# OpenMPPT2-Supply.net
KiCad netlist of a schematic drawn in Altium Designer
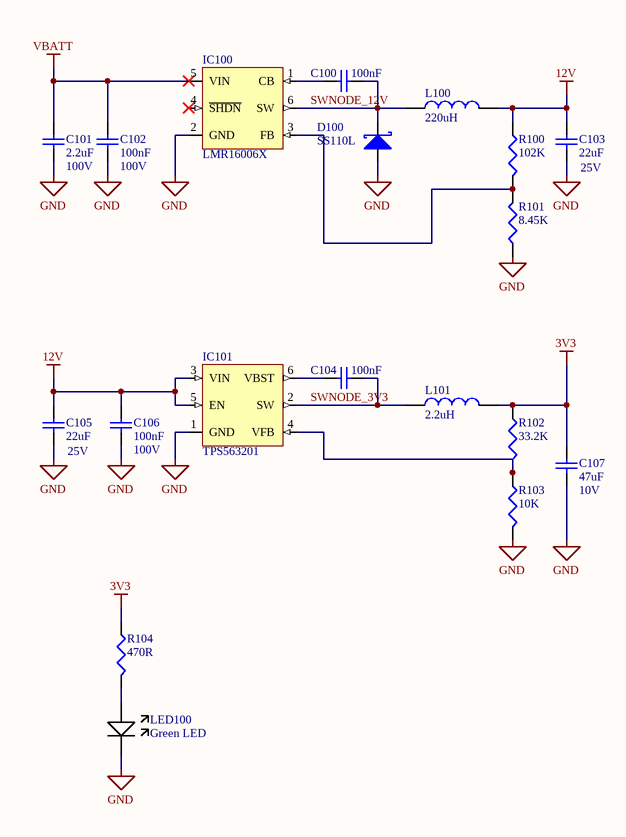
[diagram p0: OpenMPPT2-Supply.SchDoc]

(export (version "E")
  (design (tool "Eeschema 10.0.6"))
  (components
    (comp (ref "C100")
      (value "100nF")
      (footprint "C-0805")
      (description "Capacitor, 100nF, 100V, X7R")
      (libsource (lib "SBT_Capacitors_Ceramic") (part "100nF/0805/CER/100V"))
    )
    (comp (ref "C101")
      (value "2.2uF")
      (footprint "C-1210")
      (description "Capacitor, 2.2uF, 100V, X7R")
      (fields (field (name "VOLTAGE RATING") "100V"))
      (libsource (lib "SBT_Capacitors_Ceramic") (part "2.2uF/1210/CER/100V"))
    )
    (comp (ref "C102")
      (value "100nF")
      (footprint "C-0805")
      (description "Capacitor, 100nF, 100V, X7R")
      (fields (field (name "VOLTAGE RATING") "100V"))
      (libsource (lib "SBT_Capacitors_Ceramic") (part "100nF/0805/CER/100V"))
    )
    (comp (ref "C103")
      (value "22uF")
      (footprint "C-1206")
      (description "Capacitor, 22uF, 25V, ±10%, X5R, C1206, T:-55°C to +85°C")
      (fields (field (name "VOLTAGE RANGE") "25V"))
      (libsource (lib "SBT_Capacitors_Ceramic") (part "22uF/1206/CER/25V"))
    )
    (comp (ref "C104")
      (value "100nF")
      (footprint "C-0805")
      (description "Capacitor, 100nF, 100V, X7R")
      (libsource (lib "SBT_Capacitors_Ceramic") (part "100nF/0805/CER/100V"))
    )
    (comp (ref "C105")
      (value "22uF")
      (footprint "C-1206")
      (description "Capacitor, 22uF, 25V, ±10%, X5R, C1206, T:-55°C to +85°C")
      (fields (field (name "VOLTAGE RANGE") "25V"))
      (libsource (lib "SBT_Capacitors_Ceramic") (part "22uF/1206/CER/25V"))
    )
    (comp (ref "C106")
      (value "100nF")
      (footprint "C-0805")
      (description "Capacitor, 100nF, 100V, X7R")
      (fields (field (name "VOLTAGE RATING") "100V"))
      (libsource (lib "SBT_Capacitors_Ceramic") (part "100nF/0805/CER/100V"))
    )
    (comp (ref "C107")
      (value "47uF")
      (footprint "C-1210")
      (description "Capacitor, 47uF, 10V, X7R")
      (fields (field (name "VOLTAGE RATING") "10V"))
      (libsource (lib "SBT_Capacitors_Ceramic") (part "47uF/1210/CER/10V"))
    )
    (comp (ref "D100")
      (value "SS110L")
      (footprint "SUB-SMA")
      (description "Diode Schottky, Vrrm: 100V, If: 1A, Vf: 0.9V")
      (libsource (lib "SBT_Diodes") (part "SS110L"))
    )
    (comp (ref "IC100")
      (value "LMR16006X")
      (footprint "SOT-23-6")
      (description "60V, 600mA Step-Down Regulator")
      (libsource (lib "SBT_ICs") (part "LMR16006X"))
    )
    (comp (ref "IC101")
      (value "TPS563201")
      (footprint "SOT-23-6")
      (description "17V Input, 3-A Synchronous Step-Down Voltage Regulator")
      (libsource (lib "SBT_ICs") (part "TPS563201"))
    )
    (comp (ref "L100")
      (value "220uH")
      (footprint "WE-PD_1050_Metal Base")
      (description "WE-PD SMD Shielded Power Inductor, size 1050, 220uH")
      (fields
        (field (name "PARTNUMBER") "7447714221")
        (field (name "Comment") "WE-PD, 7447714221")
        (field (name "PUBLISHER") "Wurth Elektronik")
      )
      (libsource (lib "ALTIUM-WE-PD-rev16b") (part "WE-PD, 7447714221"))
    )
    (comp (ref "L101")
      (value "2.2uH")
      (footprint "WE-PD_7332_Metal Base")
      (description "WE-PD SMD Shielded Power Inductor, size 7332, 2.2uH")
      (fields
        (field (name "PARTNUMBER") "744778002")
        (field (name "Comment") "WE-PD, 744778002")
        (field (name "PUBLISHER") "Wurth Elektronik")
      )
      (libsource (lib "ALTIUM-WE-PD-rev16b") (part "WE-PD, 744778002"))
    )
    (comp (ref "LED100")
      (value "Green LED")
      (footprint "0603")
      (description "LED, Green, 0603")
      (libsource (lib "SBT_LEDs") (part "KPT-1608SGC"))
    )
    (comp (ref "R100")
      (value "102K")
      (footprint "0603")
      (description "Resistor, 102K, 1%, 0.063W, 50V, 100PPM, 0603")
      (libsource (lib "SBT_Resistors_SMD") (part "102K/0603/0100W/75V"))
    )
    (comp (ref "R101")
      (value "8.45K")
      (footprint "0603")
      (description "Resistor, 8.45K, 1%, 0.1W, 75V, 100PPM, 0603")
      (libsource (lib "SBT_Resistors_SMD") (part "8.45K/0603/0100W/75V"))
    )
    (comp (ref "R102")
      (value "33.2K")
      (footprint "0603")
      (description "Resistor, 33.2K, 1%, 0.063W, 50V, 100PPM, 0603")
      (libsource (lib "SBT_Resistors_SMD") (part "33.2K/0603/0063W/50V"))
    )
    (comp (ref "R103")
      (value "10K")
      (footprint "0603")
      (description "Resistor, 10K, 1%, 0.063W, 50V, 100PPM, 0603")
      (libsource (lib "SBT_Resistors_SMD") (part "10K/0603/0063W/50V"))
    )
    (comp (ref "R104")
      (value "470R")
      (footprint "0603")
      (description "Resistor, 470R, 1%, 0.125W, 50V, 100PPM, 0603")
      (libsource (lib "SBT_Resistors_SMD") (part "470/0603/0125W/50V"))
    )
  )
  (nets
    (net (code "1") (name "/SWNODE_3V3") (class "Default")
      (node (ref "C104") (pin "2") (pinfunction "2_2") (pintype "passive"))
      (node (ref "IC101") (pin "2") (pinfunction "SW_2") (pintype "output"))
      (node (ref "L101") (pin "1") (pinfunction "1_1") (pintype "passive"))
    )
    (net (code "2") (name "/SWNODE_12V") (class "Default")
      (node (ref "C100") (pin "2") (pinfunction "2_2") (pintype "passive"))
      (node (ref "D100") (pin "2") (pinfunction "K_2") (pintype "passive"))
      (node (ref "IC100") (pin "6") (pinfunction "SW_6") (pintype "output"))
      (node (ref "L100") (pin "1") (pinfunction "1_1") (pintype "passive"))
    )
    (net (code "3") (name "3V3") (class "Default")
      (node (ref "C107") (pin "1") (pinfunction "1_1") (pintype "passive"))
      (node (ref "L101") (pin "2") (pinfunction "2_2") (pintype "passive"))
      (node (ref "R102") (pin "1") (pinfunction "1_1") (pintype "passive"))
      (node (ref "R104") (pin "1") (pinfunction "1_1") (pintype "passive"))
    )
    (net (code "4") (name "12V") (class "Default")
      (node (ref "C103") (pin "1") (pinfunction "1_1") (pintype "passive"))
      (node (ref "C105") (pin "1") (pinfunction "1_1") (pintype "passive"))
      (node (ref "C106") (pin "2") (pinfunction "2_2") (pintype "passive"))
      (node (ref "IC101") (pin "3") (pinfunction "VIN_3") (pintype "input"))
      (node (ref "IC101") (pin "5") (pinfunction "EN_5") (pintype "input"))
      (node (ref "L100") (pin "2") (pinfunction "2_2") (pintype "passive"))
      (node (ref "R100") (pin "1") (pinfunction "1_1") (pintype "passive"))
    )
    (net (code "5") (name "GND") (class "Default")
      (node (ref "C101") (pin "1") (pinfunction "1_1") (pintype "passive"))
      (node (ref "C102") (pin "1") (pinfunction "1_1") (pintype "passive"))
      (node (ref "C103") (pin "2") (pinfunction "2_2") (pintype "passive"))
      (node (ref "C105") (pin "2") (pinfunction "2_2") (pintype "passive"))
      (node (ref "C106") (pin "1") (pinfunction "1_1") (pintype "passive"))
      (node (ref "C107") (pin "2") (pinfunction "2_2") (pintype "passive"))
      (node (ref "D100") (pin "1") (pinfunction "A_1") (pintype "passive"))
      (node (ref "IC100") (pin "2") (pinfunction "GND_2") (pintype "power_in"))
      (node (ref "IC101") (pin "1") (pinfunction "GND_1") (pintype "power_in"))
      (node (ref "LED100") (pin "K") (pinfunction "K_K") (pintype "power_in"))
      (node (ref "R101") (pin "1") (pinfunction "1_1") (pintype "passive"))
      (node (ref "R103") (pin "2") (pinfunction "2_2") (pintype "passive"))
    )
    (net (code "6") (name "Net-(IC100-CB)") (class "Default")
      (node (ref "C100") (pin "1") (pinfunction "1_1") (pintype "passive"))
      (node (ref "IC100") (pin "1") (pinfunction "CB_1") (pintype "input"))
    )
    (net (code "7") (name "Net-(IC100-FB)") (class "Default")
      (node (ref "IC100") (pin "3") (pinfunction "FB_3") (pintype "input"))
      (node (ref "R100") (pin "2") (pinfunction "2_2") (pintype "passive"))
      (node (ref "R101") (pin "2") (pinfunction "2_2") (pintype "passive"))
    )
    (net (code "8") (name "Net-(IC101-VBST)") (class "Default")
      (node (ref "C104") (pin "1") (pinfunction "1_1") (pintype "passive"))
      (node (ref "IC101") (pin "6") (pinfunction "VBST_6") (pintype "output"))
    )
    (net (code "9") (name "Net-(IC101-VFB)") (class "Default")
      (node (ref "IC101") (pin "4") (pinfunction "VFB_4") (pintype "input"))
      (node (ref "R102") (pin "2") (pinfunction "2_2") (pintype "passive"))
      (node (ref "R103") (pin "1") (pinfunction "1_1") (pintype "passive"))
    )
    (net (code "10") (name "Net-(LED100-PadA)") (class "Default")
      (node (ref "LED100") (pin "A") (pinfunction "A_A") (pintype "power_in"))
      (node (ref "R104") (pin "2") (pinfunction "2_2") (pintype "passive"))
    )
    (net (code "11") (name "VBATT") (class "Default")
      (node (ref "C101") (pin "2") (pinfunction "2_2") (pintype "passive"))
      (node (ref "C102") (pin "2") (pinfunction "2_2") (pintype "passive"))
      (node (ref "IC100") (pin "5") (pinfunction "VIN_5") (pintype "power_in"))
    )
    (net (code "12") (name "unconnected-(IC100-~{SHDN}-Pad4)") (class "Default")
      (node (ref "IC100") (pin "4") (pinfunction "~{SHDN}_4") (pintype "input+no_connect"))
    )
  )
)
